# BareBones.net
KiCad netlist of a schematic drawn in EAGLE
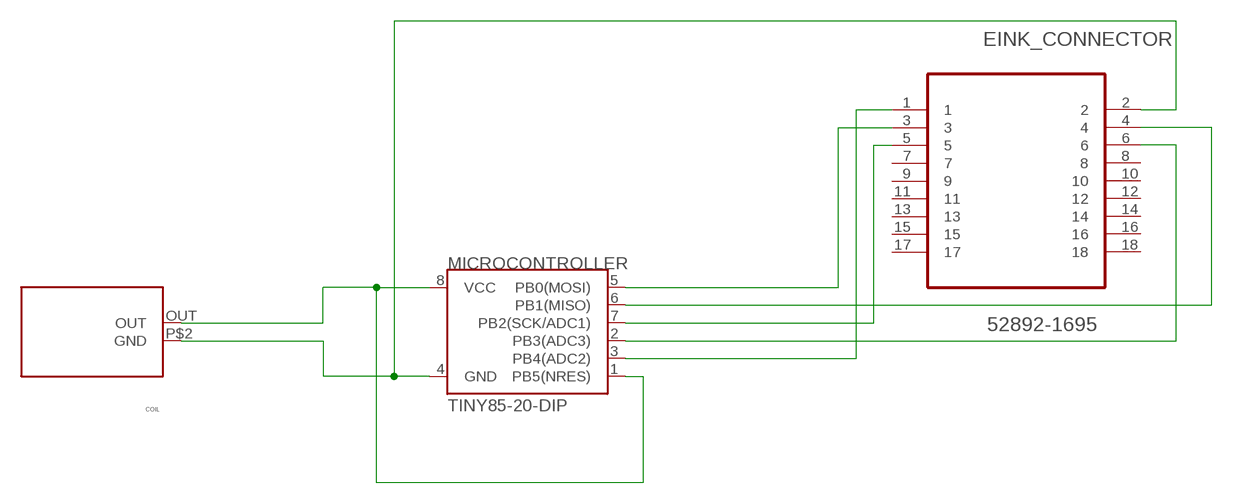
[diagram p0: schematic, sheet 1]

(export (version "E")
  (design (tool "Eeschema 10.0.6"))
  (components
    (comp (ref "COIL")
      (value "P9027LP-R")
      (footprint "eagle-import:P9027LP-R")
      (libsource (lib "eagle-import") (part "P9027LP-R"))
    )
    (comp (ref "EINK_CONNECTOR")
      (value "52892-1695")
      (footprint "eagle-import:MOLEX_52892-1695")
      (libsource (lib "eagle-import") (part "52892-1695"))
    )
    (comp (ref "MICROCONTROLLER")
      (value "TINY85-20-DIP")
      (footprint "eagle-import:DIP08")
      (libsource (lib "eagle-import") (part "ATTINY45TINY85-20-DIP"))
    )
  )
  (nets
    (net (code "1") (name "Net-(COIL-GND)") (class "Default")
      (node (ref "COIL") (pin "P$2") (pinfunction "GND_P$2") (pintype "power_in"))
      (node (ref "EINK_CONNECTOR") (pin "2") (pinfunction "2_2") (pintype "passive"))
      (node (ref "MICROCONTROLLER") (pin "4") (pinfunction "GND_4") (pintype "bidirectional"))
    )
    (net (code "2") (name "Net-(MICROCONTROLLER-PB0(MOSI))") (class "Default")
      (node (ref "EINK_CONNECTOR") (pin "3") (pinfunction "3_3") (pintype "passive"))
      (node (ref "MICROCONTROLLER") (pin "5") (pinfunction "PB0(MOSI)_5") (pintype "bidirectional"))
    )
    (net (code "3") (name "Net-(MICROCONTROLLER-PB1(MISO))") (class "Default")
      (node (ref "EINK_CONNECTOR") (pin "4") (pinfunction "4_4") (pintype "passive"))
      (node (ref "MICROCONTROLLER") (pin "6") (pinfunction "PB1(MISO)_6") (pintype "bidirectional"))
    )
    (net (code "4") (name "Net-(MICROCONTROLLER-PB2(SCK{slash}ADC1))") (class "Default")
      (node (ref "EINK_CONNECTOR") (pin "5") (pinfunction "5_5") (pintype "passive"))
      (node (ref "MICROCONTROLLER") (pin "7") (pinfunction "PB2(SCK/ADC1)_7") (pintype "bidirectional"))
    )
    (net (code "5") (name "Net-(MICROCONTROLLER-PB3(ADC3))") (class "Default")
      (node (ref "EINK_CONNECTOR") (pin "6") (pinfunction "6_6") (pintype "passive"))
      (node (ref "MICROCONTROLLER") (pin "2") (pinfunction "PB3(ADC3)_2") (pintype "bidirectional"))
    )
    (net (code "6") (name "Net-(MICROCONTROLLER-PB4(ADC2))") (class "Default")
      (node (ref "EINK_CONNECTOR") (pin "1") (pinfunction "1_1") (pintype "passive"))
      (node (ref "MICROCONTROLLER") (pin "3") (pinfunction "PB4(ADC2)_3") (pintype "bidirectional"))
    )
    (net (code "7") (name "Net-(MICROCONTROLLER-PB5(NRES))") (class "Default")
      (node (ref "COIL") (pin "OUT") (pinfunction "OUT_OUT") (pintype "power_in"))
      (node (ref "MICROCONTROLLER") (pin "1") (pinfunction "PB5(NRES)_1") (pintype "bidirectional"))
      (node (ref "MICROCONTROLLER") (pin "8") (pinfunction "VCC_8") (pintype "bidirectional"))
    )
    (net (code "8") (name "unconnected-(EINK_CONNECTOR-Pad7)") (class "Default")
      (node (ref "EINK_CONNECTOR") (pin "7") (pinfunction "7_7") (pintype "passive"))
    )
    (net (code "9") (name "unconnected-(EINK_CONNECTOR-Pad8)") (class "Default")
      (node (ref "EINK_CONNECTOR") (pin "8") (pinfunction "8_8") (pintype "passive"))
    )
    (net (code "10") (name "unconnected-(EINK_CONNECTOR-Pad9)") (class "Default")
      (node (ref "EINK_CONNECTOR") (pin "9") (pinfunction "9_9") (pintype "passive"))
    )
    (net (code "11") (name "unconnected-(EINK_CONNECTOR-Pad10)") (class "Default")
      (node (ref "EINK_CONNECTOR") (pin "10") (pinfunction "10_10") (pintype "passive"))
    )
    (net (code "12") (name "unconnected-(EINK_CONNECTOR-Pad11)") (class "Default")
      (node (ref "EINK_CONNECTOR") (pin "11") (pinfunction "11_11") (pintype "passive"))
    )
    (net (code "13") (name "unconnected-(EINK_CONNECTOR-Pad12)") (class "Default")
      (node (ref "EINK_CONNECTOR") (pin "12") (pinfunction "12_12") (pintype "passive"))
    )
    (net (code "14") (name "unconnected-(EINK_CONNECTOR-Pad13)") (class "Default")
      (node (ref "EINK_CONNECTOR") (pin "13") (pinfunction "13_13") (pintype "passive"))
    )
    (net (code "15") (name "unconnected-(EINK_CONNECTOR-Pad14)") (class "Default")
      (node (ref "EINK_CONNECTOR") (pin "14") (pinfunction "14_14") (pintype "passive"))
    )
    (net (code "16") (name "unconnected-(EINK_CONNECTOR-Pad15)") (class "Default")
      (node (ref "EINK_CONNECTOR") (pin "15") (pinfunction "15_15") (pintype "passive"))
    )
    (net (code "17") (name "unconnected-(EINK_CONNECTOR-Pad16)") (class "Default")
      (node (ref "EINK_CONNECTOR") (pin "16") (pinfunction "16_16") (pintype "passive"))
    )
    (net (code "18") (name "unconnected-(EINK_CONNECTOR-Pad17)") (class "Default")
      (node (ref "EINK_CONNECTOR") (pin "17") (pinfunction "17_17") (pintype "passive"))
    )
    (net (code "19") (name "unconnected-(EINK_CONNECTOR-Pad18)") (class "Default")
      (node (ref "EINK_CONNECTOR") (pin "18") (pinfunction "18_18") (pintype "passive"))
    )
  )
)
